# nixie_thermometer.net
KiCad netlist of a schematic drawn in EAGLE
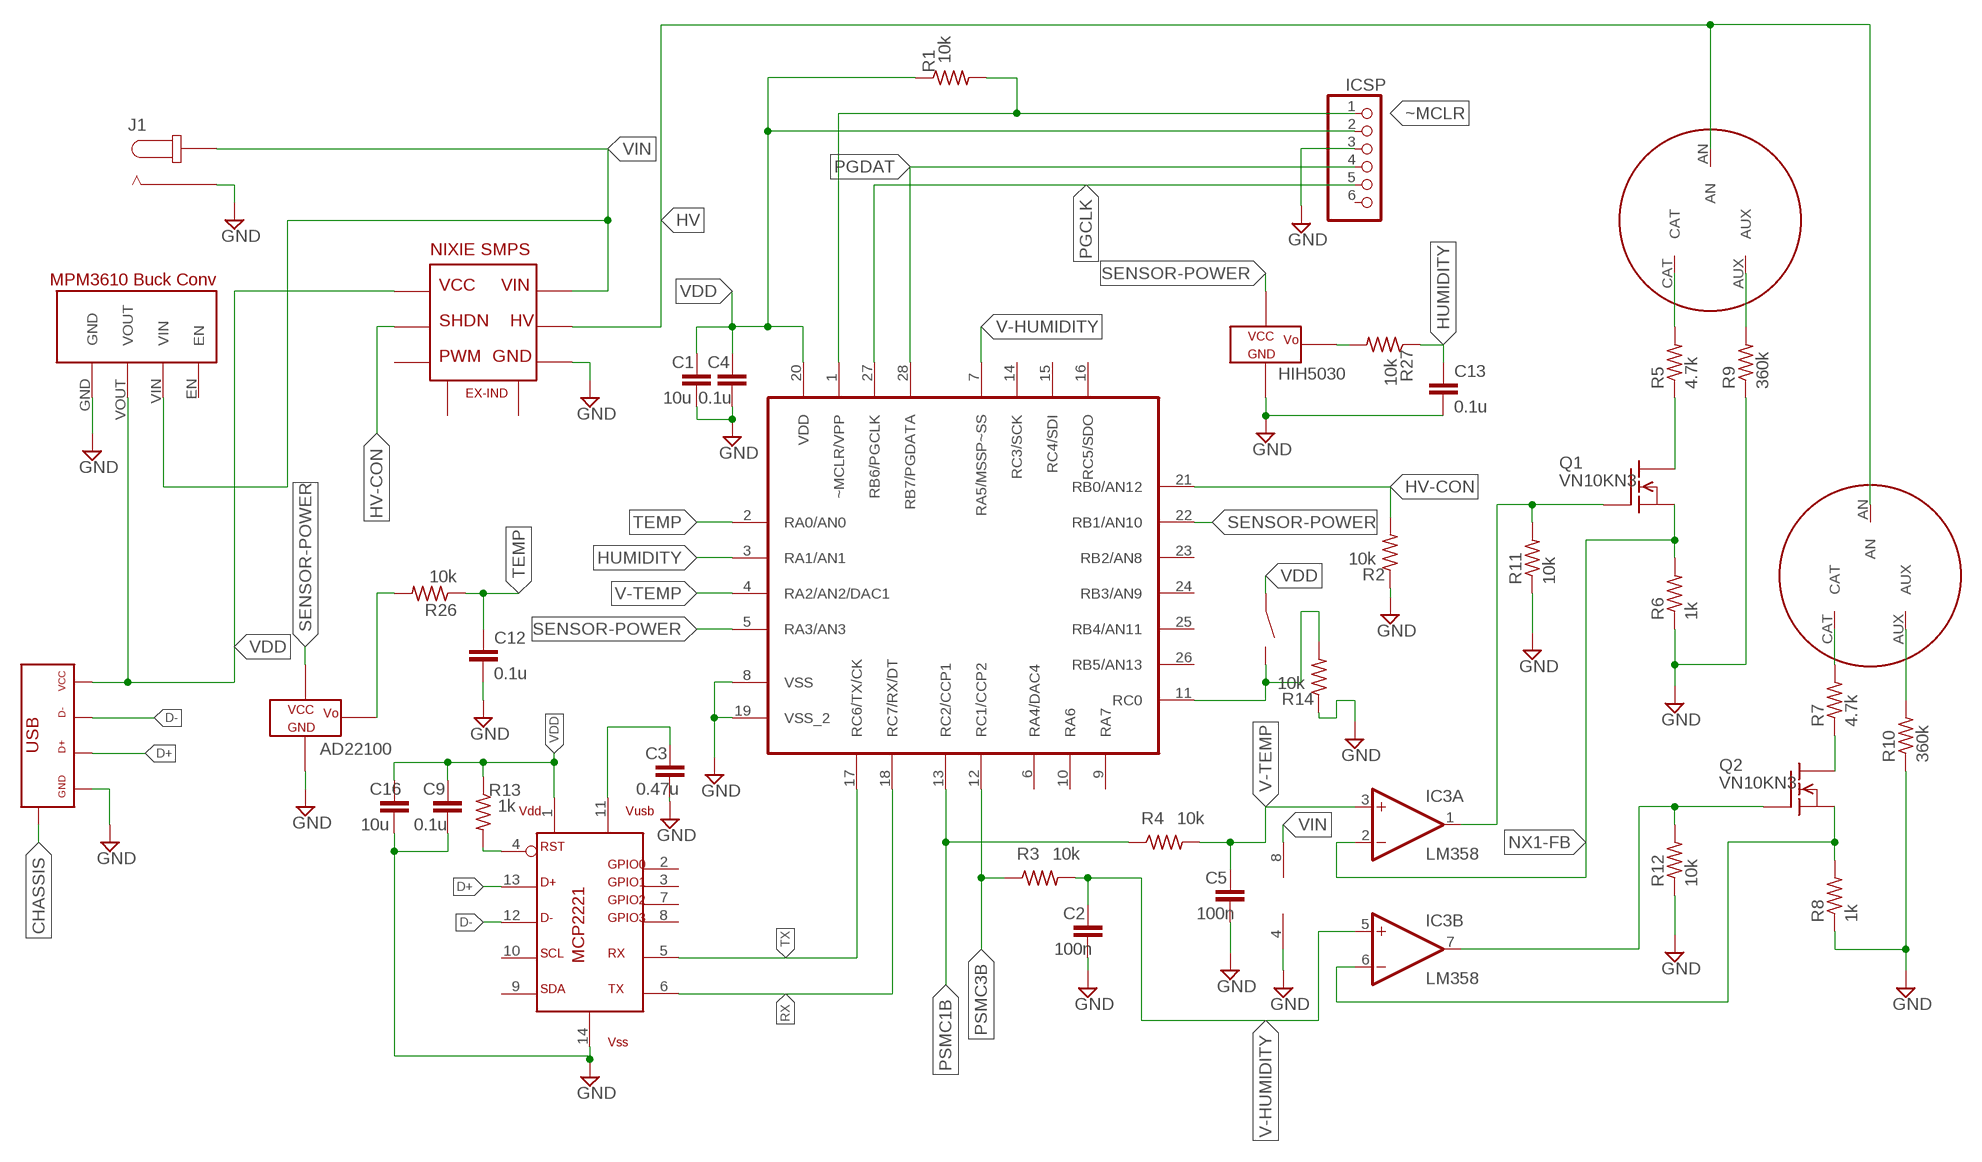
[diagram p0: schematic, sheet 1]

(export (version "E")
  (design (tool "Eeschema 10.0.6"))
  (components
    (comp (ref "AD22100")
      (value "AD22100")
      (footprint "eagle-import:TO-92")
      (libsource (lib "eagle-import") (part "AD22100"))
    )
    (comp (ref "C1")
      (value "10u")
      (footprint "eagle-import:C0805")
      (libsource (lib "eagle-import") (part "C-EUC0805"))
    )
    (comp (ref "C2")
      (value "100n")
      (footprint "eagle-import:C0805")
      (libsource (lib "eagle-import") (part "C-EUC0805"))
    )
    (comp (ref "C3")
      (value "0.47u")
      (footprint "eagle-import:C0805")
      (libsource (lib "eagle-import") (part "C-EUC0805"))
    )
    (comp (ref "C4")
      (value "0.1u")
      (footprint "eagle-import:C0805")
      (libsource (lib "eagle-import") (part "C-EUC0805"))
    )
    (comp (ref "C5")
      (value "100n")
      (footprint "eagle-import:C0805")
      (libsource (lib "eagle-import") (part "C-EUC0805"))
    )
    (comp (ref "C9")
      (value "0.1u")
      (footprint "eagle-import:C0805")
      (libsource (lib "eagle-import") (part "C-EUC0805"))
    )
    (comp (ref "C12")
      (value "0.1u")
      (footprint "eagle-import:C1206")
      (libsource (lib "eagle-import") (part "C1206"))
    )
    (comp (ref "C13")
      (value "0.1u")
      (footprint "eagle-import:C1206")
      (libsource (lib "eagle-import") (part "C1206"))
    )
    (comp (ref "C16")
      (value "10u")
      (footprint "eagle-import:C0805")
      (libsource (lib "eagle-import") (part "C-EUC0805"))
    )
    (comp (ref "HIH5030")
      (value "HIH5030")
      (footprint "eagle-import:HIH5030")
      (libsource (lib "eagle-import") (part "HIH5030"))
    )
    (comp (ref "IC1")
      (value "PIC16F1788")
      (footprint "eagle-import:DIP-28")
      (fields (field (name "MPN") "PIC16F876-04/SP"))
      (libsource (lib "eagle-import") (part "PIC16F1788"))
    )
    (comp (ref "IC2")
      (value "MCP2221")
      (footprint "eagle-import:SOIC-14")
      (libsource (lib "eagle-import") (part "MCP2221"))
    )
    (comp (ref "IC3")
      (value "LM358")
      (footprint "eagle-import:DIP-8")
      (libsource (lib "eagle-import") (part "LM358"))
    )
    (comp (ref "ICSP")
      (value "PINHD-1X6")
      (footprint "eagle-import:1X06")
      (libsource (lib "eagle-import") (part "PINHD-1X6"))
    )
    (comp (ref "J1")
      (value "CONN-DC-JACK-PANEL")
      (footprint "eagle-import:DC-JACK")
      (libsource (lib "eagle-import") (part "CONN-DC-JACK-PANEL"))
    )
    (comp (ref "Q1")
      (value "VN10KN3")
      (footprint "eagle-import:TO-92")
      (libsource (lib "eagle-import") (part "VN10KN3"))
    )
    (comp (ref "Q2")
      (value "VN10KN3")
      (footprint "eagle-import:TO-92")
      (libsource (lib "eagle-import") (part "VN10KN3"))
    )
    (comp (ref "R1")
      (value "10k")
      (footprint "eagle-import:R0805")
      (libsource (lib "eagle-import") (part "R0805"))
    )
    (comp (ref "R2")
      (value "10k")
      (footprint "eagle-import:R0805")
      (libsource (lib "eagle-import") (part "R0805"))
    )
    (comp (ref "R3")
      (value "10k")
      (footprint "eagle-import:R0805")
      (libsource (lib "eagle-import") (part "R0805"))
    )
    (comp (ref "R4")
      (value "10k")
      (footprint "eagle-import:R0805")
      (libsource (lib "eagle-import") (part "R0805"))
    )
    (comp (ref "R5")
      (value "4.7k")
      (footprint "eagle-import:R0204_7")
      (libsource (lib "eagle-import") (part "R0204/7"))
    )
    (comp (ref "R6")
      (value "1k")
      (footprint "eagle-import:R0204_7")
      (libsource (lib "eagle-import") (part "R0204/7"))
    )
    (comp (ref "R7")
      (value "4.7k")
      (footprint "eagle-import:R0204_7")
      (libsource (lib "eagle-import") (part "R0204/7"))
    )
    (comp (ref "R8")
      (value "1k")
      (footprint "eagle-import:R0204_7")
      (libsource (lib "eagle-import") (part "R0204/7"))
    )
    (comp (ref "R9")
      (value "360k")
      (footprint "eagle-import:R0204_7")
      (libsource (lib "eagle-import") (part "R0204/7"))
    )
    (comp (ref "R10")
      (value "360k")
      (footprint "eagle-import:R0204_7")
      (libsource (lib "eagle-import") (part "R0204/7"))
    )
    (comp (ref "R11")
      (value "10k")
      (footprint "eagle-import:R0204_7")
      (libsource (lib "eagle-import") (part "R0204/7"))
    )
    (comp (ref "R12")
      (value "10k")
      (footprint "eagle-import:R0204_7")
      (libsource (lib "eagle-import") (part "R0204/7"))
    )
    (comp (ref "R13")
      (value "1k")
      (footprint "eagle-import:R0805")
      (libsource (lib "eagle-import") (part "R0805"))
    )
    (comp (ref "R14")
      (value "10k")
      (footprint "eagle-import:R0805")
      (libsource (lib "eagle-import") (part "R0805"))
    )
    (comp (ref "R26")
      (value "10k")
      (footprint "eagle-import:R0805")
      (libsource (lib "eagle-import") (part "R0805"))
    )
    (comp (ref "R27")
      (value "10k")
      (footprint "eagle-import:R0805")
      (libsource (lib "eagle-import") (part "R0805"))
    )
    (comp (ref "U$1")
      (value "MPM3610-ADAFRUIT")
      (footprint "eagle-import:MPM3610-ADAFRUIT-MODULE")
      (libsource (lib "eagle-import") (part "MPM3610-ADAFRUIT"))
    )
    (comp (ref "U$2")
      (value "SMPS-HV-MODULE")
      (footprint "eagle-import:SMPS-HV-MOD-MODULE")
      (libsource (lib "eagle-import") (part "SMPS-HV-MODULE"))
    )
    (comp (ref "U$3")
      (value "IN-13")
      (footprint "eagle-import:IN-13")
      (libsource (lib "eagle-import") (part "IN-13"))
    )
    (comp (ref "U$4")
      (value "IN-13")
      (footprint "eagle-import:IN-13")
      (libsource (lib "eagle-import") (part "IN-13"))
    )
    (comp (ref "U$5")
      (value "SW-SPST-PUSHBUTTONSMD")
      (footprint "eagle-import:SW-SPST-PUSHBUTTON-UNKNOWN-SMD")
      (libsource (lib "eagle-import") (part "SW-SPST-PUSHBUTTONSMD"))
    )
    (comp (ref "USB$2")
      (value "USB-MILLMAX-896-43-004")
      (footprint "eagle-import:USB-MILLMAX-896-43-004-90")
      (libsource (lib "eagle-import") (part "USB-MILLMAX-896-43-004"))
    )
  )
  (nets
    (net (code "1") (name "/~{MCLR}") (class "Default")
      (node (ref "IC1") (pin "1") (pinfunction "~{MCLR/VPP}_1") (pintype "input"))
      (node (ref "ICSP") (pin "1") (pinfunction "1_1") (pintype "passive"))
      (node (ref "R1") (pin "2") (pinfunction "2_2") (pintype "passive"))
    )
    (net (code "2") (name "CHASSIS") (class "Default")
      (node (ref "USB$2") (pin "P$5") (pinfunction "SHIELD_P$5") (pintype "bidirectional"))
      (node (ref "USB$2") (pin "P$6") (pinfunction "SHIELD_P$6") (pintype "bidirectional"))
    )
    (net (code "3") (name "D+") (class "Default")
      (node (ref "IC2") (pin "13") (pinfunction "DP_13") (pintype "bidirectional"))
      (node (ref "USB$2") (pin "D+") (pinfunction "D+_D+") (pintype "bidirectional"))
    )
    (net (code "4") (name "D-") (class "Default")
      (node (ref "IC2") (pin "12") (pinfunction "DM_12") (pintype "bidirectional"))
      (node (ref "USB$2") (pin "D-") (pinfunction "D-_D-") (pintype "bidirectional"))
    )
    (net (code "5") (name "GND") (class "Default")
      (node (ref "AD22100") (pin "3") (pinfunction "GND_3") (pintype "bidirectional"))
      (node (ref "C1") (pin "2") (pinfunction "2_2") (pintype "passive"))
      (node (ref "C12") (pin "2") (pinfunction "2_2") (pintype "passive"))
      (node (ref "C13") (pin "2") (pinfunction "2_2") (pintype "passive"))
      (node (ref "C16") (pin "2") (pinfunction "2_2") (pintype "passive"))
      (node (ref "C2") (pin "2") (pinfunction "2_2") (pintype "passive"))
      (node (ref "C3") (pin "2") (pinfunction "2_2") (pintype "passive"))
      (node (ref "C4") (pin "2") (pinfunction "2_2") (pintype "passive"))
      (node (ref "C5") (pin "2") (pinfunction "2_2") (pintype "passive"))
      (node (ref "C9") (pin "2") (pinfunction "2_2") (pintype "passive"))
      (node (ref "HIH5030") (pin "GND") (pinfunction "GND_GND") (pintype "bidirectional"))
      (node (ref "IC1") (pin "19") (pinfunction "VSS_2_19") (pintype "power_in"))
      (node (ref "IC1") (pin "8") (pinfunction "VSS_8") (pintype "power_in"))
      (node (ref "IC2") (pin "14") (pinfunction "VSS_14") (pintype "power_in"))
      (node (ref "IC3") (pin "4") (pinfunction "V-_4") (pintype "power_in"))
      (node (ref "ICSP") (pin "3") (pinfunction "3_3") (pintype "passive"))
      (node (ref "J1") (pin "GND-BOT") (pinfunction "GND_GND-BOT") (pintype "passive"))
      (node (ref "J1") (pin "GND-TOP") (pinfunction "GND_GND-TOP") (pintype "passive"))
      (node (ref "R10") (pin "1") (pinfunction "1_1") (pintype "passive"))
      (node (ref "R11") (pin "1") (pinfunction "1_1") (pintype "passive"))
      (node (ref "R12") (pin "1") (pinfunction "1_1") (pintype "passive"))
      (node (ref "R14") (pin "1") (pinfunction "1_1") (pintype "passive"))
      (node (ref "R2") (pin "1") (pinfunction "1_1") (pintype "passive"))
      (node (ref "R6") (pin "1") (pinfunction "1_1") (pintype "passive"))
      (node (ref "R8") (pin "1") (pinfunction "1_1") (pintype "passive"))
      (node (ref "R9") (pin "1") (pinfunction "1_1") (pintype "passive"))
      (node (ref "U$1") (pin "GND") (pinfunction "GND_GND") (pintype "bidirectional"))
      (node (ref "U$2") (pin "GND") (pinfunction "GND_GND") (pintype "bidirectional"))
      (node (ref "U$2") (pin "GND-HV") (pinfunction "GND_GND-HV") (pintype "bidirectional"))
      (node (ref "USB$2") (pin "GND") (pinfunction "GND_GND") (pintype "bidirectional"))
    )
    (net (code "6") (name "HUMIDITY") (class "Default")
      (node (ref "C13") (pin "1") (pinfunction "1_1") (pintype "passive"))
      (node (ref "IC1") (pin "3") (pinfunction "RA1/AN1_3") (pintype "bidirectional"))
      (node (ref "R27") (pin "1") (pinfunction "1_1") (pintype "passive"))
    )
    (net (code "7") (name "HV") (class "Default")
      (node (ref "U$2") (pin "HV") (pinfunction "HV_HV") (pintype "bidirectional"))
      (node (ref "U$3") (pin "AN") (pinfunction "AN_AN") (pintype "bidirectional"))
      (node (ref "U$4") (pin "AN") (pinfunction "AN_AN") (pintype "bidirectional"))
    )
    (net (code "8") (name "HV-CON") (class "Default")
      (node (ref "IC1") (pin "21") (pinfunction "RB0/AN12_21") (pintype "bidirectional"))
      (node (ref "R2") (pin "2") (pinfunction "2_2") (pintype "passive"))
      (node (ref "U$2") (pin "SHDN") (pinfunction "SHDN_SHDN") (pintype "bidirectional"))
    )
    (net (code "9") (name "NX1-FB") (class "Default")
      (node (ref "IC3") (pin "2") (pinfunction "-IN_2") (pintype "input"))
      (node (ref "Q1") (pin "1") (pinfunction "S_1") (pintype "passive"))
      (node (ref "R6") (pin "2") (pinfunction "2_2") (pintype "passive"))
    )
    (net (code "10") (name "Net-(AD22100-VO)") (class "Default")
      (node (ref "AD22100") (pin "2") (pinfunction "VO_2") (pintype "bidirectional"))
      (node (ref "R26") (pin "2") (pinfunction "2_2") (pintype "passive"))
    )
    (net (code "11") (name "Net-(HIH5030-PadVO)") (class "Default")
      (node (ref "HIH5030") (pin "VO") (pinfunction "VO_VO") (pintype "bidirectional"))
      (node (ref "R27") (pin "2") (pinfunction "2_2") (pintype "passive"))
    )
    (net (code "12") (name "Net-(IC1-RC0)") (class "Default")
      (node (ref "IC1") (pin "11") (pinfunction "RC0_11") (pintype "bidirectional"))
      (node (ref "R14") (pin "2") (pinfunction "2_2") (pintype "passive"))
      (node (ref "U$5") (pin "P$6") (pinfunction "P$2_P$6") (pintype "bidirectional"))
      (node (ref "U$5") (pin "P$8") (pinfunction "P$2_P$8") (pintype "bidirectional"))
    )
    (net (code "13") (name "Net-(IC2-RST)") (class "Default")
      (node (ref "IC2") (pin "4") (pinfunction "RST_4") (pintype "input"))
      (node (ref "R13") (pin "2") (pinfunction "2_2") (pintype "passive"))
    )
    (net (code "14") (name "Net-(IC2-VUSB)") (class "Default")
      (node (ref "C3") (pin "1") (pinfunction "1_1") (pintype "passive"))
      (node (ref "IC2") (pin "11") (pinfunction "VUSB_11") (pintype "bidirectional"))
    )
    (net (code "15") (name "Net-(IC3A-OUT)") (class "Default")
      (node (ref "IC3") (pin "1") (pinfunction "OUT_1") (pintype "output"))
      (node (ref "Q1") (pin "2") (pinfunction "G_2") (pintype "passive"))
      (node (ref "R11") (pin "2") (pinfunction "2_2") (pintype "passive"))
    )
    (net (code "16") (name "Net-(IC3B--IN)") (class "Default")
      (node (ref "IC3") (pin "6") (pinfunction "-IN_6") (pintype "input"))
      (node (ref "Q2") (pin "1") (pinfunction "S_1") (pintype "passive"))
      (node (ref "R8") (pin "2") (pinfunction "2_2") (pintype "passive"))
    )
    (net (code "17") (name "Net-(IC3B-OUT)") (class "Default")
      (node (ref "IC3") (pin "7") (pinfunction "OUT_7") (pintype "output"))
      (node (ref "Q2") (pin "2") (pinfunction "G_2") (pintype "passive"))
      (node (ref "R12") (pin "2") (pinfunction "2_2") (pintype "passive"))
    )
    (net (code "18") (name "Net-(Q1-D)") (class "Default")
      (node (ref "Q1") (pin "3") (pinfunction "D_3") (pintype "passive"))
      (node (ref "R5") (pin "1") (pinfunction "1_1") (pintype "passive"))
    )
    (net (code "19") (name "Net-(Q2-D)") (class "Default")
      (node (ref "Q2") (pin "3") (pinfunction "D_3") (pintype "passive"))
      (node (ref "R7") (pin "1") (pinfunction "1_1") (pintype "passive"))
    )
    (net (code "20") (name "Net-(R5-Pad2)") (class "Default")
      (node (ref "R5") (pin "2") (pinfunction "2_2") (pintype "passive"))
      (node (ref "U$3") (pin "CAT") (pinfunction "CAT_CAT") (pintype "bidirectional"))
    )
    (net (code "21") (name "Net-(R7-Pad2)") (class "Default")
      (node (ref "R7") (pin "2") (pinfunction "2_2") (pintype "passive"))
      (node (ref "U$4") (pin "CAT") (pinfunction "CAT_CAT") (pintype "bidirectional"))
    )
    (net (code "22") (name "Net-(R9-Pad2)") (class "Default")
      (node (ref "R9") (pin "2") (pinfunction "2_2") (pintype "passive"))
      (node (ref "U$3") (pin "AUX") (pinfunction "AUX_AUX") (pintype "bidirectional"))
    )
    (net (code "23") (name "Net-(R10-Pad2)") (class "Default")
      (node (ref "R10") (pin "2") (pinfunction "2_2") (pintype "passive"))
      (node (ref "U$4") (pin "AUX") (pinfunction "AUX_AUX") (pintype "bidirectional"))
    )
    (net (code "24") (name "PGCLK") (class "Default")
      (node (ref "IC1") (pin "27") (pinfunction "RB6/PGCLK_27") (pintype "input"))
      (node (ref "ICSP") (pin "5") (pinfunction "5_5") (pintype "passive"))
    )
    (net (code "25") (name "PGDAT") (class "Default")
      (node (ref "IC1") (pin "28") (pinfunction "RB7/PGDATA_28") (pintype "input"))
      (node (ref "ICSP") (pin "4") (pinfunction "4_4") (pintype "passive"))
    )
    (net (code "26") (name "PSMC1B") (class "Default")
      (node (ref "IC1") (pin "13") (pinfunction "RC2/CCP1_13") (pintype "bidirectional"))
      (node (ref "R4") (pin "1") (pinfunction "1_1") (pintype "passive"))
    )
    (net (code "27") (name "PSMC3B") (class "Default")
      (node (ref "IC1") (pin "12") (pinfunction "RC1/CCP2_12") (pintype "bidirectional"))
      (node (ref "R3") (pin "1") (pinfunction "1_1") (pintype "passive"))
    )
    (net (code "28") (name "RX") (class "Default")
      (node (ref "IC1") (pin "18") (pinfunction "RC7/RX/DT_18") (pintype "bidirectional"))
      (node (ref "IC2") (pin "6") (pinfunction "TX_6") (pintype "output"))
    )
    (net (code "29") (name "SENSOR-POWER") (class "Default")
      (node (ref "AD22100") (pin "1") (pinfunction "VCC_1") (pintype "bidirectional"))
      (node (ref "HIH5030") (pin "VCC") (pinfunction "VCC_VCC") (pintype "bidirectional"))
      (node (ref "IC1") (pin "22") (pinfunction "RB1/AN10_22") (pintype "bidirectional"))
      (node (ref "IC1") (pin "5") (pinfunction "RA3/AN3_5") (pintype "bidirectional"))
    )
    (net (code "30") (name "TEMP") (class "Default")
      (node (ref "C12") (pin "1") (pinfunction "1_1") (pintype "passive"))
      (node (ref "IC1") (pin "2") (pinfunction "RA0/AN0_2") (pintype "bidirectional"))
      (node (ref "R26") (pin "1") (pinfunction "1_1") (pintype "passive"))
    )
    (net (code "31") (name "TX") (class "Default")
      (node (ref "IC1") (pin "17") (pinfunction "RC6/TX/CK_17") (pintype "bidirectional"))
      (node (ref "IC2") (pin "5") (pinfunction "RX_5") (pintype "input"))
    )
    (net (code "32") (name "V-HUMIDITY") (class "Default")
      (node (ref "C2") (pin "1") (pinfunction "1_1") (pintype "passive"))
      (node (ref "IC1") (pin "7") (pinfunction "RA5/MSSP~{SS}_7") (pintype "bidirectional"))
      (node (ref "IC3") (pin "5") (pinfunction "+IN_5") (pintype "input"))
      (node (ref "R3") (pin "2") (pinfunction "2_2") (pintype "passive"))
    )
    (net (code "33") (name "V-TEMP") (class "Default")
      (node (ref "C5") (pin "1") (pinfunction "1_1") (pintype "passive"))
      (node (ref "IC1") (pin "4") (pinfunction "RA2/AN2/DAC1_4") (pintype "bidirectional"))
      (node (ref "IC3") (pin "3") (pinfunction "+IN_3") (pintype "input"))
      (node (ref "R4") (pin "2") (pinfunction "2_2") (pintype "passive"))
    )
    (net (code "34") (name "VDD") (class "Default")
      (node (ref "C1") (pin "1") (pinfunction "1_1") (pintype "passive"))
      (node (ref "C16") (pin "1") (pinfunction "1_1") (pintype "passive"))
      (node (ref "C4") (pin "1") (pinfunction "1_1") (pintype "passive"))
      (node (ref "C9") (pin "1") (pinfunction "1_1") (pintype "passive"))
      (node (ref "IC1") (pin "20") (pinfunction "VDD_20") (pintype "power_in"))
      (node (ref "IC2") (pin "1") (pinfunction "VDD_1") (pintype "power_in"))
      (node (ref "ICSP") (pin "2") (pinfunction "2_2") (pintype "passive"))
      (node (ref "R1") (pin "1") (pinfunction "1_1") (pintype "passive"))
      (node (ref "R13") (pin "1") (pinfunction "1_1") (pintype "passive"))
      (node (ref "U$1") (pin "VOUT") (pinfunction "VOUT_VOUT") (pintype "bidirectional"))
      (node (ref "U$2") (pin "VDD") (pinfunction "VCC_VDD") (pintype "bidirectional"))
      (node (ref "U$5") (pin "P$5") (pinfunction "P$1_P$5") (pintype "bidirectional"))
      (node (ref "U$5") (pin "P$7") (pinfunction "P$1_P$7") (pintype "bidirectional"))
      (node (ref "USB$2") (pin "VCC") (pinfunction "VCC_VCC") (pintype "bidirectional"))
    )
    (net (code "35") (name "VIN") (class "Default")
      (node (ref "IC3") (pin "8") (pinfunction "V+_8") (pintype "power_in"))
      (node (ref "J1") (pin "POW-BOT") (pinfunction "POW_POW-BOT") (pintype "passive"))
      (node (ref "J1") (pin "POW-TOP") (pinfunction "POW_POW-TOP") (pintype "passive"))
      (node (ref "U$1") (pin "VIN") (pinfunction "VIN_VIN") (pintype "bidirectional"))
      (node (ref "U$2") (pin "VIN") (pinfunction "VIN_VIN") (pintype "bidirectional"))
    )
    (net (code "36") (name "unconnected-(IC1-RA4{slash}DAC4-Pad6)") (class "Default")
      (node (ref "IC1") (pin "6") (pinfunction "RA4/DAC4_6") (pintype "bidirectional"))
    )
    (net (code "37") (name "unconnected-(IC1-RA6-Pad10)") (class "Default")
      (node (ref "IC1") (pin "10") (pinfunction "RA6_10") (pintype "bidirectional"))
    )
    (net (code "38") (name "unconnected-(IC1-RA7-Pad9)") (class "Default")
      (node (ref "IC1") (pin "9") (pinfunction "RA7_9") (pintype "bidirectional"))
    )
    (net (code "39") (name "unconnected-(IC1-RB2{slash}AN8-Pad23)") (class "Default")
      (node (ref "IC1") (pin "23") (pinfunction "RB2/AN8_23") (pintype "bidirectional"))
    )
    (net (code "40") (name "unconnected-(IC1-RB3{slash}AN9-Pad24)") (class "Default")
      (node (ref "IC1") (pin "24") (pinfunction "RB3/AN9_24") (pintype "bidirectional"))
    )
    (net (code "41") (name "unconnected-(IC1-RB4{slash}AN11-Pad25)") (class "Default")
      (node (ref "IC1") (pin "25") (pinfunction "RB4/AN11_25") (pintype "bidirectional"))
    )
    (net (code "42") (name "unconnected-(IC1-RB5{slash}AN13-Pad26)") (class "Default")
      (node (ref "IC1") (pin "26") (pinfunction "RB5/AN13_26") (pintype "bidirectional"))
    )
    (net (code "43") (name "unconnected-(IC1-RC3{slash}SCK-Pad14)") (class "Default")
      (node (ref "IC1") (pin "14") (pinfunction "RC3/SCK_14") (pintype "bidirectional"))
    )
    (net (code "44") (name "unconnected-(IC1-RC4{slash}SDI-Pad15)") (class "Default")
      (node (ref "IC1") (pin "15") (pinfunction "RC4/SDI_15") (pintype "bidirectional"))
    )
    (net (code "45") (name "unconnected-(IC1-RC5{slash}SDO-Pad16)") (class "Default")
      (node (ref "IC1") (pin "16") (pinfunction "RC5/SDO_16") (pintype "bidirectional"))
    )
    (net (code "46") (name "unconnected-(IC2-GPIO0-Pad2)") (class "Default")
      (node (ref "IC2") (pin "2") (pinfunction "GPIO0_2") (pintype "bidirectional"))
    )
    (net (code "47") (name "unconnected-(IC2-GPIO1-Pad3)") (class "Default")
      (node (ref "IC2") (pin "3") (pinfunction "GPIO1_3") (pintype "bidirectional"))
    )
    (net (code "48") (name "unconnected-(IC2-GPIO2-Pad7)") (class "Default")
      (node (ref "IC2") (pin "7") (pinfunction "GPIO2_7") (pintype "bidirectional"))
    )
    (net (code "49") (name "unconnected-(IC2-GPIO3-Pad8)") (class "Default")
      (node (ref "IC2") (pin "8") (pinfunction "GPIO3_8") (pintype "bidirectional"))
    )
    (net (code "50") (name "unconnected-(IC2-SCL-Pad10)") (class "Default")
      (node (ref "IC2") (pin "10") (pinfunction "SCL_10") (pintype "output"))
    )
    (net (code "51") (name "unconnected-(IC2-SDA-Pad9)") (class "Default")
      (node (ref "IC2") (pin "9") (pinfunction "SDA_9") (pintype "bidirectional"))
    )
    (net (code "52") (name "unconnected-(ICSP-Pad6)") (class "Default")
      (node (ref "ICSP") (pin "6") (pinfunction "6_6") (pintype "passive"))
    )
    (net (code "53") (name "unconnected-(U$1-PadEN)") (class "Default")
      (node (ref "U$1") (pin "EN") (pinfunction "EN_EN") (pintype "bidirectional"))
    )
    (net (code "54") (name "unconnected-(U$2-P$1-PadEX-IND0)") (class "Default")
      (node (ref "U$2") (pin "EX-IND0") (pinfunction "P$1_EX-IND0") (pintype "bidirectional"))
    )
    (net (code "55") (name "unconnected-(U$2-P$2-PadEX-INT1)") (class "Default")
      (node (ref "U$2") (pin "EX-INT1") (pinfunction "P$2_EX-INT1") (pintype "bidirectional"))
    )
    (net (code "56") (name "unconnected-(U$2-PadOUTPUT)") (class "Default")
      (node (ref "U$2") (pin "OUTPUT") (pinfunction "OUTPUT_OUTPUT") (pintype "bidirectional"))
    )
  )
)
